# ALU_Zeros.net
KiCad netlist of a schematic drawn in Altium Designer
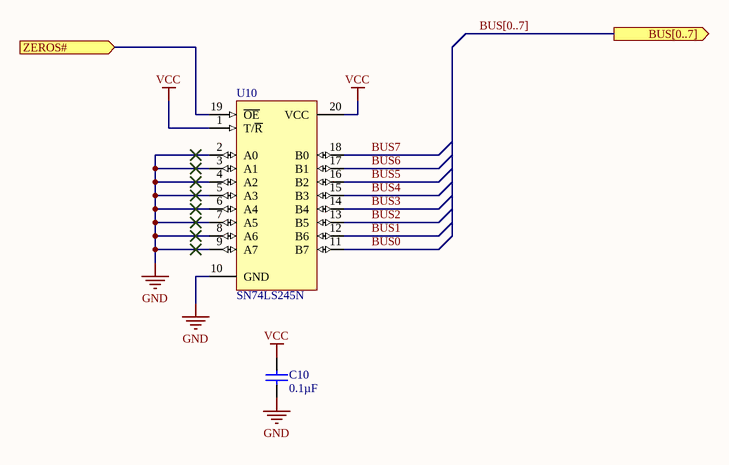
[diagram p0: ALU_Zeros.SchDoc]

(export (version "E")
  (design (tool "Eeschema 10.0.6"))
  (components
    (comp (ref "C10")
      (value "K104K15X7RF5TL2")
      (footprint "VISH-K104K15X7RF5TL2")
      (description "Ceramic Capacitor, 100 nF, +/- 10%, 50 V, -55 to 125 degC, 2-Pin THD, RoHS, Tape and Reel")
      (fields
        (field (name "MANUFACTURER") "Vishay")
        (field (name "TOLERANCE") "±10%")
        (field (name "CAPACITANCE") "0.1µF")
      )
      (libsource (lib "Altium Content Vault") (part "CAP-NP-2"))
    )
    (comp (ref "U10")
      (value "SN74LS245N")
      (footprint "N020")
      (description "Octal Bus Transceiver with 3-State Outputs")
      (fields (field (name "PUBLISHER") "Altium Limited"))
      (libsource (lib "TI Interface 8-Bit Line Transceiver") (part "SN74LS245N"))
    )
  )
  (nets
    (net (code "1") (name "/BUS0") (class "Default")
      (node (ref "U10") (pin "11") (pinfunction "B7_11") (pintype "bidirectional"))
    )
    (net (code "2") (name "/BUS1") (class "Default")
      (node (ref "U10") (pin "12") (pinfunction "B6_12") (pintype "bidirectional"))
    )
    (net (code "3") (name "/BUS2") (class "Default")
      (node (ref "U10") (pin "13") (pinfunction "B5_13") (pintype "bidirectional"))
    )
    (net (code "4") (name "/BUS3") (class "Default")
      (node (ref "U10") (pin "14") (pinfunction "B4_14") (pintype "bidirectional"))
    )
    (net (code "5") (name "/BUS4") (class "Default")
      (node (ref "U10") (pin "15") (pinfunction "B3_15") (pintype "bidirectional"))
    )
    (net (code "6") (name "/BUS5") (class "Default")
      (node (ref "U10") (pin "16") (pinfunction "B2_16") (pintype "bidirectional"))
    )
    (net (code "7") (name "/BUS6") (class "Default")
      (node (ref "U10") (pin "17") (pinfunction "B1_17") (pintype "bidirectional"))
    )
    (net (code "8") (name "/BUS7") (class "Default")
      (node (ref "U10") (pin "18") (pinfunction "B0_18") (pintype "bidirectional"))
    )
    (net (code "10") (name "/ZEROS#") (class "Default")
      (node (ref "U10") (pin "19") (pinfunction "~{OE}_19") (pintype "input"))
    )
    (net (code "11") (name "GND") (class "Default")
      (node (ref "C10") (pin "2") (pinfunction "2_2") (pintype "passive"))
      (node (ref "U10") (pin "10") (pinfunction "GND_10") (pintype "power_in"))
      (node (ref "U10") (pin "2") (pinfunction "A0_2") (pintype "bidirectional"))
      (node (ref "U10") (pin "3") (pinfunction "A1_3") (pintype "bidirectional"))
      (node (ref "U10") (pin "4") (pinfunction "A2_4") (pintype "bidirectional"))
      (node (ref "U10") (pin "5") (pinfunction "A3_5") (pintype "bidirectional"))
      (node (ref "U10") (pin "6") (pinfunction "A4_6") (pintype "bidirectional"))
      (node (ref "U10") (pin "7") (pinfunction "A5_7") (pintype "bidirectional"))
      (node (ref "U10") (pin "8") (pinfunction "A6_8") (pintype "bidirectional"))
      (node (ref "U10") (pin "9") (pinfunction "A7_9") (pintype "bidirectional"))
    )
    (net (code "12") (name "VCC") (class "Default")
      (node (ref "C10") (pin "1") (pinfunction "1_1") (pintype "passive"))
      (node (ref "U10") (pin "1") (pinfunction "T/~{R}_1") (pintype "input"))
      (node (ref "U10") (pin "20") (pinfunction "VCC_20") (pintype "power_in"))
    )
  )
)
